# Priemnic.net
KiCad netlist of a schematic drawn in Altium Designer
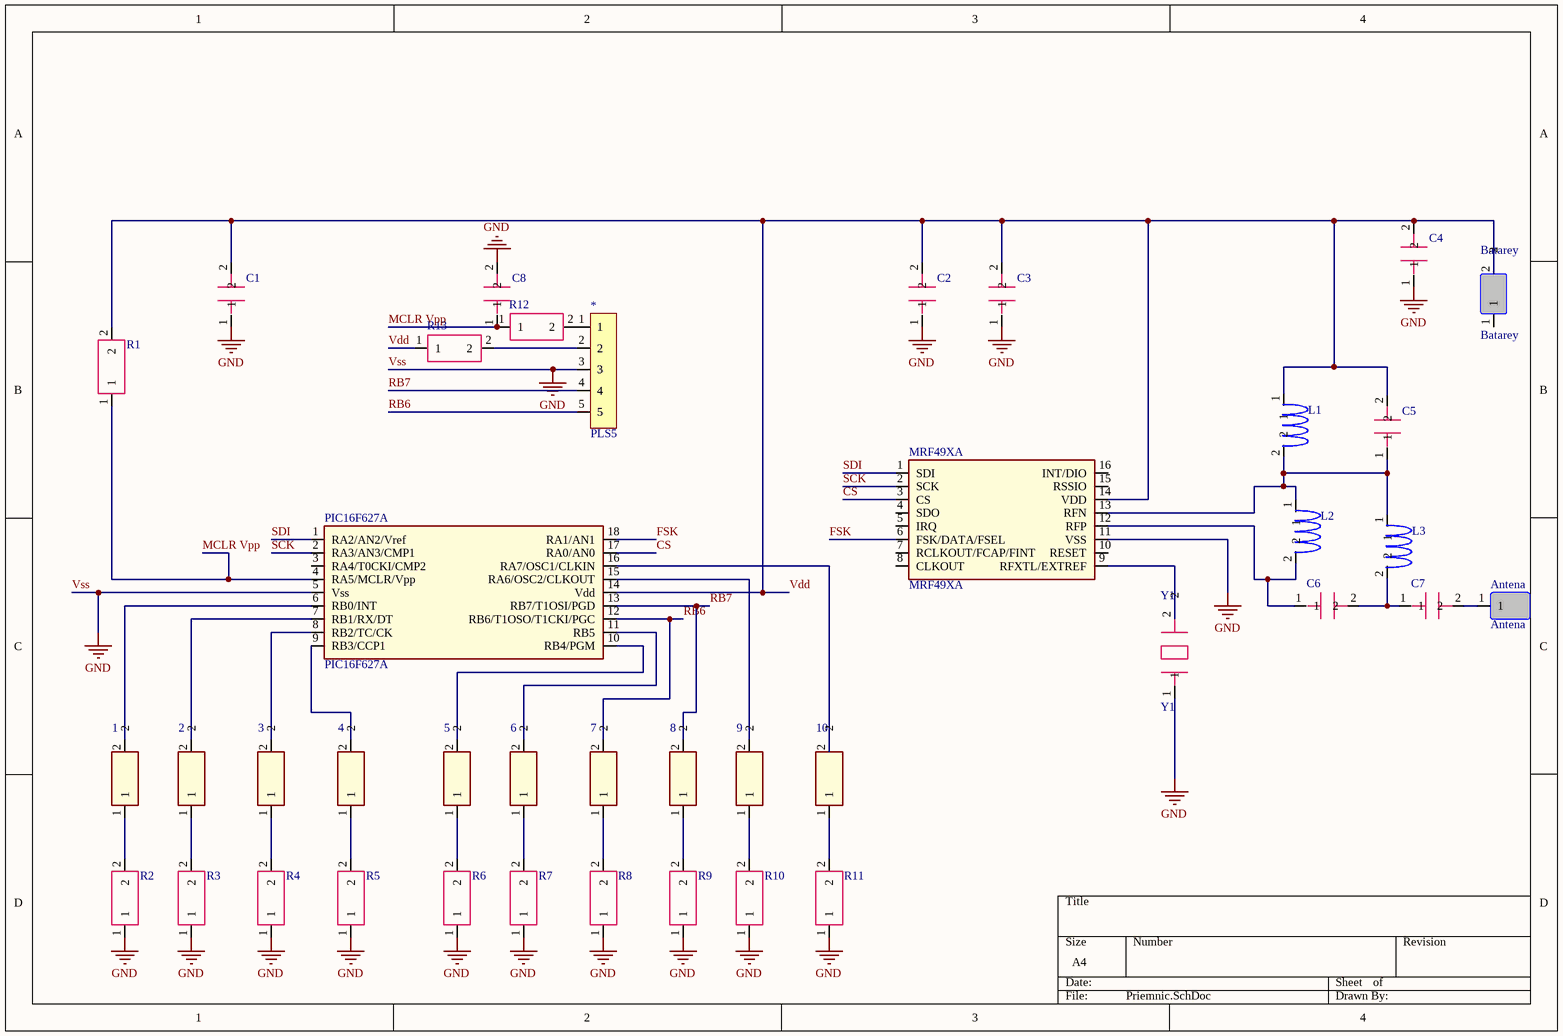
[diagram p0: Priemnic.SchDoc]

(export (version "E")
  (design (tool "Eeschema 10.0.6"))
  (components
    (comp (ref "*") (value "PLS5") (footprint "RCU:PLS5") (libsource (lib "RCU") (part "PLS5")))
    (comp (ref "1")
      (value "~")
      (footprint "RCU:Light-emitting diode")
      (libsource (lib "RCU") (part "Light-emitting diode"))
    )
    (comp (ref "2")
      (value "~")
      (footprint "RCU:Light-emitting diode")
      (libsource (lib "RCU") (part "Light-emitting diode"))
    )
    (comp (ref "3")
      (value "~")
      (footprint "RCU:Light-emitting diode")
      (libsource (lib "RCU") (part "Light-emitting diode"))
    )
    (comp (ref "4")
      (value "~")
      (footprint "RCU:Light-emitting diode")
      (libsource (lib "RCU") (part "Light-emitting diode"))
    )
    (comp (ref "5")
      (value "~")
      (footprint "RCU:Light-emitting diode")
      (libsource (lib "RCU") (part "Light-emitting diode"))
    )
    (comp (ref "6")
      (value "~")
      (footprint "RCU:Light-emitting diode")
      (libsource (lib "RCU") (part "Light-emitting diode"))
    )
    (comp (ref "7")
      (value "~")
      (footprint "RCU:Light-emitting diode")
      (libsource (lib "RCU") (part "Light-emitting diode"))
    )
    (comp (ref "8")
      (value "~")
      (footprint "RCU:Light-emitting diode")
      (libsource (lib "RCU") (part "Light-emitting diode"))
    )
    (comp (ref "9")
      (value "~")
      (footprint "RCU:Light-emitting diode")
      (libsource (lib "RCU") (part "Light-emitting diode"))
    )
    (comp (ref "10")
      (value "~")
      (footprint "RCU:Light-emitting diode")
      (libsource (lib "RCU") (part "Light-emitting diode"))
    )
    (comp (ref "Antena") (value "Antena") (footprint "RCU:Anteny") (libsource (lib "RCU") (part "Antena")))
    (comp (ref "Batarey")
      (value "Batarey")
      (footprint "RCU:Batarey")
      (libsource (lib "RCU") (part "Batarey"))
    )
    (comp (ref "C1") (value "~") (footprint "RCU:С0805") (libsource (lib "RCU") (part "Capacity")))
    (comp (ref "C2") (value "~") (footprint "RCU:С0805") (libsource (lib "RCU") (part "Capacity")))
    (comp (ref "C3") (value "~") (footprint "RCU:С0805") (libsource (lib "RCU") (part "Capacity")))
    (comp (ref "C4") (value "~") (footprint "RCU:С0805") (libsource (lib "RCU") (part "Capacity")))
    (comp (ref "C5") (value "~") (footprint "RCU:С0805") (libsource (lib "RCU") (part "Capacity")))
    (comp (ref "C6") (value "~") (footprint "RCU:С0805") (libsource (lib "RCU") (part "Capacity")))
    (comp (ref "C7") (value "~") (footprint "RCU:С0805") (libsource (lib "RCU") (part "Capacity")))
    (comp (ref "C8") (value "~") (footprint "RCU:С0805") (libsource (lib "RCU") (part "Capacity")))
    (comp (ref "L1") (value "~") (footprint "RCU:L?") (libsource (lib "RCU") (part "Inductance")))
    (comp (ref "L2") (value "~") (footprint "RCU:L?") (libsource (lib "RCU") (part "Inductance")))
    (comp (ref "L3") (value "~") (footprint "RCU:L?") (libsource (lib "RCU") (part "Inductance")))
    (comp (ref "MRF49XA")
      (value "MRF49XA")
      (footprint "RCU:MRF49XA")
      (libsource (lib "RCU") (part "MRF49XA"))
    )
    (comp (ref "PIC16F627A")
      (value "PIC16F627A")
      (footprint "RCU:PIC16F627A")
      (libsource (lib "RCU") (part "PIC16F627A"))
    )
    (comp (ref "R1") (value "~") (footprint "RCU:R0805") (libsource (lib "RCU") (part "Rezistor")))
    (comp (ref "R2") (value "~") (footprint "RCU:R0805") (libsource (lib "RCU") (part "Rezistor")))
    (comp (ref "R3") (value "~") (footprint "RCU:R0805") (libsource (lib "RCU") (part "Rezistor")))
    (comp (ref "R4") (value "~") (footprint "RCU:R0805") (libsource (lib "RCU") (part "Rezistor")))
    (comp (ref "R5") (value "~") (footprint "RCU:R0805") (libsource (lib "RCU") (part "Rezistor")))
    (comp (ref "R6") (value "~") (footprint "RCU:R0805") (libsource (lib "RCU") (part "Rezistor")))
    (comp (ref "R7") (value "~") (footprint "RCU:R0805") (libsource (lib "RCU") (part "Rezistor")))
    (comp (ref "R8") (value "~") (footprint "RCU:R0805") (libsource (lib "RCU") (part "Rezistor")))
    (comp (ref "R9") (value "~") (footprint "RCU:R0805") (libsource (lib "RCU") (part "Rezistor")))
    (comp (ref "R10") (value "~") (footprint "RCU:R0805") (libsource (lib "RCU") (part "Rezistor")))
    (comp (ref "R11") (value "~") (footprint "RCU:R0805") (libsource (lib "RCU") (part "Rezistor")))
    (comp (ref "R12") (value "~") (footprint "RCU:R0805") (libsource (lib "RCU") (part "Rezistor")))
    (comp (ref "R13") (value "~") (footprint "RCU:R0805") (libsource (lib "RCU") (part "Rezistor")))
    (comp (ref "Y1") (value "Y1") (footprint "RCU:Quartz") (libsource (lib "RCU") (part "Quartz")))
  )
  (nets
    (net (code "1") (name "/CS") (class "Default")
      (node (ref "MRF49XA") (pin "3") (pinfunction "CS_3") (pintype "passive"))
      (node (ref "PIC16F627A") (pin "17") (pinfunction "RA0/AN0_17") (pintype "passive"))
    )
    (net (code "2") (name "/FSK") (class "Default")
      (node (ref "MRF49XA") (pin "6") (pinfunction "FSK/DATA/FSEL_6") (pintype "passive"))
      (node (ref "PIC16F627A") (pin "18") (pinfunction "RA1/AN1_18") (pintype "passive"))
    )
    (net (code "3") (name "/MCLR Vpp") (class "Default")
      (node (ref "C8") (pin "1") (pinfunction "1_1") (pintype "passive"))
      (node (ref "PIC16F627A") (pin "4") (pinfunction "RA5/MCLR/Vpp_4") (pintype "passive"))
      (node (ref "R1") (pin "1") (pinfunction "1_1") (pintype "passive"))
      (node (ref "R12") (pin "1") (pinfunction "1_1") (pintype "passive"))
    )
    (net (code "4") (name "/RB6") (class "Default")
      (node (ref "*") (pin "5") (pinfunction "5_5") (pintype "passive"))
      (node (ref "PIC16F627A") (pin "12") (pinfunction "RB6/T1OSO/T1CKI/PGC_12") (pintype "passive"))
    )
    (net (code "5") (name "/RB7") (class "Default")
      (node (ref "*") (pin "4") (pinfunction "4_4") (pintype "passive"))
      (node (ref "PIC16F627A") (pin "13") (pinfunction "RB7/T1OSI/PGD_13") (pintype "passive"))
    )
    (net (code "6") (name "/SCK") (class "Default")
      (node (ref "MRF49XA") (pin "2") (pinfunction "SCK_2") (pintype "passive"))
      (node (ref "PIC16F627A") (pin "2") (pinfunction "RA3/AN3/CMP1_2") (pintype "passive"))
    )
    (net (code "7") (name "/SDI") (class "Default")
      (node (ref "MRF49XA") (pin "1") (pinfunction "SDI_1") (pintype "passive"))
      (node (ref "PIC16F627A") (pin "1") (pinfunction "RA2/AN2/Vref_1") (pintype "passive"))
    )
    (net (code "8") (name "/Vdd") (class "Default")
      (node (ref "Batarey") (pin "2") (pinfunction "2_2") (pintype "passive"))
      (node (ref "C1") (pin "2") (pinfunction "2_2") (pintype "passive"))
      (node (ref "C2") (pin "2") (pinfunction "2_2") (pintype "passive"))
      (node (ref "C3") (pin "2") (pinfunction "2_2") (pintype "passive"))
      (node (ref "C4") (pin "2") (pinfunction "2_2") (pintype "passive"))
      (node (ref "C5") (pin "2") (pinfunction "2_2") (pintype "passive"))
      (node (ref "L1") (pin "1") (pinfunction "1_1") (pintype "passive"))
      (node (ref "MRF49XA") (pin "14") (pinfunction "VDD_14") (pintype "passive"))
      (node (ref "PIC16F627A") (pin "14") (pinfunction "Vdd_14") (pintype "passive"))
      (node (ref "R1") (pin "2") (pinfunction "2_2") (pintype "passive"))
      (node (ref "R13") (pin "1") (pinfunction "1_1") (pintype "passive"))
    )
    (net (code "9") (name "GND") (class "Default")
      (node (ref "*") (pin "3") (pinfunction "3_3") (pintype "passive"))
      (node (ref "C1") (pin "1") (pinfunction "1_1") (pintype "passive"))
      (node (ref "C2") (pin "1") (pinfunction "1_1") (pintype "passive"))
      (node (ref "C3") (pin "1") (pinfunction "1_1") (pintype "passive"))
      (node (ref "C4") (pin "1") (pinfunction "1_1") (pintype "passive"))
      (node (ref "C8") (pin "2") (pinfunction "2_2") (pintype "passive"))
      (node (ref "MRF49XA") (pin "11") (pinfunction "VSS_11") (pintype "passive"))
      (node (ref "PIC16F627A") (pin "5") (pinfunction "Vss_5") (pintype "passive"))
      (node (ref "R10") (pin "1") (pinfunction "1_1") (pintype "passive"))
      (node (ref "R11") (pin "1") (pinfunction "1_1") (pintype "passive"))
      (node (ref "R2") (pin "1") (pinfunction "1_1") (pintype "passive"))
      (node (ref "R3") (pin "1") (pinfunction "1_1") (pintype "passive"))
      (node (ref "R4") (pin "1") (pinfunction "1_1") (pintype "passive"))
      (node (ref "R5") (pin "1") (pinfunction "1_1") (pintype "passive"))
      (node (ref "R6") (pin "1") (pinfunction "1_1") (pintype "passive"))
      (node (ref "R7") (pin "1") (pinfunction "1_1") (pintype "passive"))
      (node (ref "R8") (pin "1") (pinfunction "1_1") (pintype "passive"))
      (node (ref "R9") (pin "1") (pinfunction "1_1") (pintype "passive"))
      (node (ref "Y1") (pin "1") (pinfunction "1_1") (pintype "passive"))
    )
    (net (code "10") (name "Net-(*-Pad1)") (class "Default")
      (node (ref "*") (pin "1") (pinfunction "1_1") (pintype "passive"))
      (node (ref "R12") (pin "2") (pinfunction "2_2") (pintype "passive"))
    )
    (net (code "11") (name "Net-(*-Pad2)") (class "Default")
      (node (ref "*") (pin "2") (pinfunction "2_2") (pintype "passive"))
      (node (ref "R13") (pin "2") (pinfunction "2_2") (pintype "passive"))
    )
    (net (code "12") (name "Net-(1-Pad1)") (class "Default")
      (node (ref "1") (pin "1") (pinfunction "1_1") (pintype "passive"))
      (node (ref "R2") (pin "2") (pinfunction "2_2") (pintype "passive"))
    )
    (net (code "13") (name "Net-(2-Pad1)") (class "Default")
      (node (ref "2") (pin "1") (pinfunction "1_1") (pintype "passive"))
      (node (ref "R3") (pin "2") (pinfunction "2_2") (pintype "passive"))
    )
    (net (code "14") (name "Net-(3-Pad1)") (class "Default")
      (node (ref "3") (pin "1") (pinfunction "1_1") (pintype "passive"))
      (node (ref "R4") (pin "2") (pinfunction "2_2") (pintype "passive"))
    )
    (net (code "15") (name "Net-(4-Pad1)") (class "Default")
      (node (ref "4") (pin "1") (pinfunction "1_1") (pintype "passive"))
      (node (ref "R5") (pin "2") (pinfunction "2_2") (pintype "passive"))
    )
    (net (code "16") (name "Net-(5-Pad1)") (class "Default")
      (node (ref "5") (pin "1") (pinfunction "1_1") (pintype "passive"))
      (node (ref "R6") (pin "2") (pinfunction "2_2") (pintype "passive"))
    )
    (net (code "17") (name "Net-(6-Pad1)") (class "Default")
      (node (ref "6") (pin "1") (pinfunction "1_1") (pintype "passive"))
      (node (ref "R7") (pin "2") (pinfunction "2_2") (pintype "passive"))
    )
    (net (code "18") (name "Net-(7-Pad1)") (class "Default")
      (node (ref "7") (pin "1") (pinfunction "1_1") (pintype "passive"))
      (node (ref "R8") (pin "2") (pinfunction "2_2") (pintype "passive"))
    )
    (net (code "19") (name "Net-(8-Pad1)") (class "Default")
      (node (ref "8") (pin "1") (pinfunction "1_1") (pintype "passive"))
      (node (ref "R9") (pin "2") (pinfunction "2_2") (pintype "passive"))
    )
    (net (code "20") (name "Net-(9-Pad1)") (class "Default")
      (node (ref "9") (pin "1") (pinfunction "1_1") (pintype "passive"))
      (node (ref "R10") (pin "2") (pinfunction "2_2") (pintype "passive"))
    )
    (net (code "21") (name "Net-(10-Pad1)") (class "Default")
      (node (ref "10") (pin "1") (pinfunction "1_1") (pintype "passive"))
      (node (ref "R11") (pin "2") (pinfunction "2_2") (pintype "passive"))
    )
    (net (code "22") (name "Net-(Antena-Pad1)") (class "Default")
      (node (ref "Antena") (pin "1") (pinfunction "1_1") (pintype "passive"))
      (node (ref "C7") (pin "2") (pinfunction "2_2") (pintype "passive"))
    )
    (net (code "23") (name "Net-(C6-Pad2)") (class "Default")
      (node (ref "C6") (pin "2") (pinfunction "2_2") (pintype "passive"))
      (node (ref "C7") (pin "1") (pinfunction "1_1") (pintype "passive"))
      (node (ref "L3") (pin "2") (pinfunction "2_2") (pintype "passive"))
    )
    (net (code "24") (name "Net-(MRF49XA-RFN)") (class "Default")
      (node (ref "C5") (pin "1") (pinfunction "1_1") (pintype "passive"))
      (node (ref "L1") (pin "2") (pinfunction "2_2") (pintype "passive"))
      (node (ref "L2") (pin "1") (pinfunction "1_1") (pintype "passive"))
      (node (ref "L3") (pin "1") (pinfunction "1_1") (pintype "passive"))
      (node (ref "MRF49XA") (pin "13") (pinfunction "RFN_13") (pintype "passive"))
    )
    (net (code "25") (name "Net-(MRF49XA-RFP)") (class "Default")
      (node (ref "C6") (pin "1") (pinfunction "1_1") (pintype "passive"))
      (node (ref "L2") (pin "2") (pinfunction "2_2") (pintype "passive"))
      (node (ref "MRF49XA") (pin "12") (pinfunction "RFP_12") (pintype "passive"))
    )
    (net (code "26") (name "Net-(MRF49XA-RFXTL{slash}EXTREF)") (class "Default")
      (node (ref "MRF49XA") (pin "9") (pinfunction "RFXTL/EXTREF_9") (pintype "passive"))
      (node (ref "Y1") (pin "2") (pinfunction "2_2") (pintype "passive"))
    )
    (net (code "27") (name "Net-(PIC16F627A-RA7{slash}OSC1{slash}CLKIN)") (class "Default")
      (node (ref "10") (pin "2") (pinfunction "2_2") (pintype "passive"))
      (node (ref "PIC16F627A") (pin "16") (pinfunction "RA7/OSC1/CLKIN_16") (pintype "passive"))
    )
    (net (code "28") (name "unconnected-(1-Pad2)") (class "Default")
      (node (ref "1") (pin "2") (pinfunction "2_2") (pintype "passive"))
    )
    (net (code "29") (name "unconnected-(2-Pad2)") (class "Default")
      (node (ref "2") (pin "2") (pinfunction "2_2") (pintype "passive"))
    )
    (net (code "30") (name "unconnected-(3-Pad2)") (class "Default")
      (node (ref "3") (pin "2") (pinfunction "2_2") (pintype "passive"))
    )
    (net (code "31") (name "unconnected-(4-Pad2)") (class "Default")
      (node (ref "4") (pin "2") (pinfunction "2_2") (pintype "passive"))
    )
    (net (code "32") (name "unconnected-(5-Pad2)") (class "Default")
      (node (ref "5") (pin "2") (pinfunction "2_2") (pintype "passive"))
    )
    (net (code "33") (name "unconnected-(6-Pad2)") (class "Default")
      (node (ref "6") (pin "2") (pinfunction "2_2") (pintype "passive"))
    )
    (net (code "34") (name "unconnected-(7-Pad2)") (class "Default")
      (node (ref "7") (pin "2") (pinfunction "2_2") (pintype "passive"))
    )
    (net (code "35") (name "unconnected-(8-Pad2)") (class "Default")
      (node (ref "8") (pin "2") (pinfunction "2_2") (pintype "passive"))
    )
    (net (code "36") (name "unconnected-(9-Pad2)") (class "Default")
      (node (ref "9") (pin "2") (pinfunction "2_2") (pintype "passive"))
    )
    (net (code "37") (name "unconnected-(Batarey-Pad1)") (class "Default")
      (node (ref "Batarey") (pin "1") (pinfunction "1_1") (pintype "passive"))
    )
    (net (code "38") (name "unconnected-(MRF49XA-CLKOUT-Pad8)") (class "Default")
      (node (ref "MRF49XA") (pin "8") (pinfunction "CLKOUT_8") (pintype "passive"))
    )
    (net (code "39") (name "unconnected-(MRF49XA-INT{slash}DIO-Pad16)") (class "Default")
      (node (ref "MRF49XA") (pin "16") (pinfunction "INT/DIO_16") (pintype "passive"))
    )
    (net (code "40") (name "unconnected-(MRF49XA-IRQ-Pad5)") (class "Default")
      (node (ref "MRF49XA") (pin "5") (pinfunction "IRQ_5") (pintype "passive"))
    )
    (net (code "41") (name "unconnected-(MRF49XA-RCLKOUT{slash}FCAP{slash}FINT-Pad7)") (class "Default")
      (node (ref "MRF49XA") (pin "7") (pinfunction "RCLKOUT/FCAP/FINT_7") (pintype "passive"))
    )
    (net (code "42") (name "unconnected-(MRF49XA-RESET-Pad10)") (class "Default")
      (node (ref "MRF49XA") (pin "10") (pinfunction "RESET_10") (pintype "passive"))
    )
    (net (code "43") (name "unconnected-(MRF49XA-RSSIO-Pad15)") (class "Default")
      (node (ref "MRF49XA") (pin "15") (pinfunction "RSSIO_15") (pintype "passive"))
    )
    (net (code "44") (name "unconnected-(MRF49XA-SDO-Pad4)") (class "Default")
      (node (ref "MRF49XA") (pin "4") (pinfunction "SDO_4") (pintype "passive"))
    )
    (net (code "45") (name "unconnected-(PIC16F627A-RA4{slash}T0CKI{slash}CMP2-Pad3)") (class "Default")
      (node (ref "PIC16F627A") (pin "3") (pinfunction "RA4/T0CKI/CMP2_3") (pintype "passive"))
    )
    (net (code "46") (name "unconnected-(PIC16F627A-RA6{slash}OSC2{slash}CLKOUT-Pad15)") (class "Default")
      (node (ref "PIC16F627A") (pin "15") (pinfunction "RA6/OSC2/CLKOUT_15") (pintype "passive"))
    )
    (net (code "47") (name "unconnected-(PIC16F627A-RB0{slash}INT-Pad6)") (class "Default")
      (node (ref "PIC16F627A") (pin "6") (pinfunction "RB0/INT_6") (pintype "passive"))
    )
    (net (code "48") (name "unconnected-(PIC16F627A-RB1{slash}RX{slash}DT-Pad7)") (class "Default")
      (node (ref "PIC16F627A") (pin "7") (pinfunction "RB1/RX/DT_7") (pintype "passive"))
    )
    (net (code "49") (name "unconnected-(PIC16F627A-RB2{slash}TC{slash}CK-Pad8)") (class "Default")
      (node (ref "PIC16F627A") (pin "8") (pinfunction "RB2/TC/CK_8") (pintype "passive"))
    )
    (net (code "50") (name "unconnected-(PIC16F627A-RB3{slash}CCP1-Pad9)") (class "Default")
      (node (ref "PIC16F627A") (pin "9") (pinfunction "RB3/CCP1_9") (pintype "passive"))
    )
    (net (code "51") (name "unconnected-(PIC16F627A-RB4{slash}PGM-Pad10)") (class "Default")
      (node (ref "PIC16F627A") (pin "10") (pinfunction "RB4/PGM_10") (pintype "passive"))
    )
    (net (code "52") (name "unconnected-(PIC16F627A-RB5-Pad11)") (class "Default")
      (node (ref "PIC16F627A") (pin "11") (pinfunction "RB5_11") (pintype "passive"))
    )
  )
)
